# RS232.net
KiCad netlist of a schematic drawn in Altium Designer
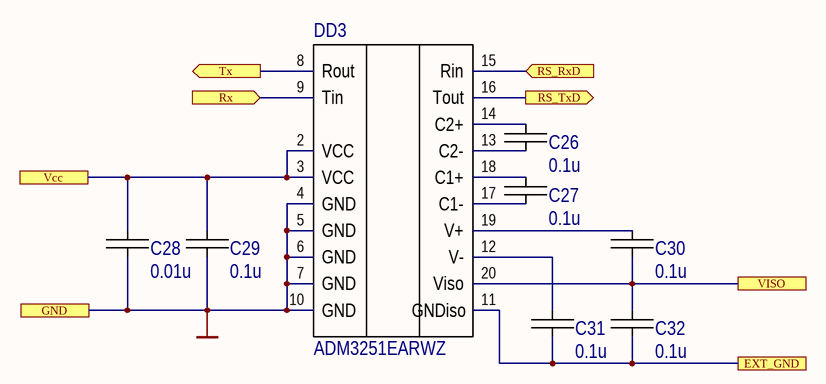
[diagram p0: RS232.SchDoc]

(export (version "E")
  (design (tool "Eeschema 10.0.6"))
  (components
    (comp (ref "C26")
      (value "0.1u")
      (footprint "C0603_IPC")
      (description "0.1uF ±10% 50V Ceramic Capacitor X7R 0603 (1608 Metric)")
      (fields (field (name "PARTNUMBER") "0.1u 50V") (field (name "MPN") "CL10B104KB8NNND"))
      (libsource (lib "DB_res_cap_ind") (part "C0603_GOST"))
    )
    (comp (ref "C27")
      (value "0.1u")
      (footprint "C0603_IPC")
      (description "0.1uF ±10% 50V Ceramic Capacitor X7R 0603 (1608 Metric)")
      (fields (field (name "PARTNUMBER") "0.1u 50V") (field (name "MPN") "CL10B104KB8NNND"))
      (libsource (lib "DB_res_cap_ind") (part "C0603_GOST"))
    )
    (comp (ref "C28")
      (value "0.01u")
      (footprint "C0603_IPC")
      (description "0.01uF ±10% 50V Ceramic Capacitor X7R 0603 (1608 Metric)")
      (fields (field (name "MPN") "CC0603KRX7R9BB103") (field (name "TOLERANCE") "0,1"))
      (libsource (lib "DB_res_cap_ind") (part "C0603_GOST"))
    )
    (comp (ref "C29")
      (value "0.1u")
      (footprint "C0603_IPC")
      (description "0.1uF ±10% 50V Ceramic Capacitor X7R 0603 (1608 Metric)")
      (fields (field (name "PARTNUMBER") "0.1u 50V") (field (name "MPN") "CL10B104KB8NNND"))
      (libsource (lib "DB_res_cap_ind") (part "C0603_GOST"))
    )
    (comp (ref "C30")
      (value "0.1u")
      (footprint "C0603_IPC")
      (description "0.1uF ±10% 50V Ceramic Capacitor X7R 0603 (1608 Metric)")
      (fields (field (name "PARTNUMBER") "0.1u 50V") (field (name "MPN") "CL10B104KB8NNND"))
      (libsource (lib "DB_res_cap_ind") (part "C0603_GOST"))
    )
    (comp (ref "C31")
      (value "0.1u")
      (footprint "C0603_IPC")
      (description "0.1uF ±10% 50V Ceramic Capacitor X7R 0603 (1608 Metric)")
      (fields (field (name "PARTNUMBER") "0.1u 50V") (field (name "MPN") "CL10B104KB8NNND"))
      (libsource (lib "DB_res_cap_ind") (part "C0603_GOST"))
    )
    (comp (ref "C32")
      (value "0.1u")
      (footprint "C0603_IPC")
      (description "0.1uF ±10% 50V Ceramic Capacitor X7R 0603 (1608 Metric)")
      (fields (field (name "PARTNUMBER") "0.1u 50V") (field (name "MPN") "CL10B104KB8NNND"))
      (libsource (lib "DB_res_cap_ind") (part "C0603_GOST"))
    )
    (comp (ref "DD3")
      (value "ADM3251EARWZ")
      (footprint "SOIC20W")
      (description "Isolated, Single-Channel RS-232 Line Driver/Receiver")
      (libsource (lib "DB_IC") (part "ADM3251E"))
    )
  )
  (nets
    (net (code "1") (name "/EXT_GND") (class "Default")
      (node (ref "C31") (pin "1") (pinfunction "1_1") (pintype "passive"))
      (node (ref "C32") (pin "1") (pinfunction "1_1") (pintype "passive"))
      (node (ref "DD3") (pin "11") (pinfunction "GNDiso_11") (pintype "passive"))
    )
    (net (code "2") (name "/RS_RxD") (class "Default")
      (node (ref "DD3") (pin "15") (pinfunction "Rin_15") (pintype "passive"))
    )
    (net (code "3") (name "/RS_TxD") (class "Default")
      (node (ref "DD3") (pin "16") (pinfunction "Tout_16") (pintype "passive"))
    )
    (net (code "4") (name "/Rx") (class "Default")
      (node (ref "DD3") (pin "9") (pinfunction "Tin_9") (pintype "passive"))
    )
    (net (code "5") (name "/Tx") (class "Default")
      (node (ref "DD3") (pin "8") (pinfunction "Rout_8") (pintype "passive"))
    )
    (net (code "6") (name "/VISO") (class "Default")
      (node (ref "C30") (pin "1") (pinfunction "1_1") (pintype "passive"))
      (node (ref "C32") (pin "2") (pinfunction "2_2") (pintype "passive"))
      (node (ref "DD3") (pin "20") (pinfunction "Viso_20") (pintype "passive"))
    )
    (net (code "7") (name "/Vcc") (class "Default")
      (node (ref "C28") (pin "1") (pinfunction "1_1") (pintype "passive"))
      (node (ref "C29") (pin "2") (pinfunction "2_2") (pintype "passive"))
      (node (ref "DD3") (pin "2") (pinfunction "VCC_2") (pintype "passive"))
      (node (ref "DD3") (pin "3") (pinfunction "VCC_3") (pintype "passive"))
    )
    (net (code "8") (name "GND") (class "Default")
      (node (ref "C28") (pin "2") (pinfunction "2_2") (pintype "passive"))
      (node (ref "C29") (pin "1") (pinfunction "1_1") (pintype "passive"))
      (node (ref "DD3") (pin "10") (pinfunction "GND_10") (pintype "passive"))
      (node (ref "DD3") (pin "4") (pinfunction "GND_4") (pintype "passive"))
      (node (ref "DD3") (pin "5") (pinfunction "GND_5") (pintype "passive"))
      (node (ref "DD3") (pin "6") (pinfunction "GND_6") (pintype "passive"))
      (node (ref "DD3") (pin "7") (pinfunction "GND_7") (pintype "passive"))
    )
    (net (code "9") (name "Net-(DD3-C1+)") (class "Default")
      (node (ref "C27") (pin "2") (pinfunction "2_2") (pintype "passive"))
      (node (ref "DD3") (pin "18") (pinfunction "C1+_18") (pintype "passive"))
    )
    (net (code "10") (name "Net-(DD3-C1-)") (class "Default")
      (node (ref "C27") (pin "1") (pinfunction "1_1") (pintype "passive"))
      (node (ref "DD3") (pin "17") (pinfunction "C1-_17") (pintype "passive"))
    )
    (net (code "11") (name "Net-(DD3-C2+)") (class "Default")
      (node (ref "C26") (pin "2") (pinfunction "2_2") (pintype "passive"))
      (node (ref "DD3") (pin "14") (pinfunction "C2+_14") (pintype "passive"))
    )
    (net (code "12") (name "Net-(DD3-C2-)") (class "Default")
      (node (ref "C26") (pin "1") (pinfunction "1_1") (pintype "passive"))
      (node (ref "DD3") (pin "13") (pinfunction "C2-_13") (pintype "passive"))
    )
    (net (code "13") (name "Net-(DD3-V+)") (class "Default")
      (node (ref "C30") (pin "2") (pinfunction "2_2") (pintype "passive"))
      (node (ref "DD3") (pin "19") (pinfunction "V+_19") (pintype "passive"))
    )
    (net (code "14") (name "Net-(DD3-V-)") (class "Default")
      (node (ref "C31") (pin "2") (pinfunction "2_2") (pintype "passive"))
      (node (ref "DD3") (pin "12") (pinfunction "V-_12") (pintype "passive"))
    )
    (net (code "15") (name "unconnected-(DD3-NC-Pad1)") (class "Default")
      (node (ref "DD3") (pin "1") (pinfunction "NC_1") (pintype "passive"))
    )
    (net (code "16") (name "unconnected-(DD3-NC-Pad2)") (class "Default")
      (node (ref "DD3") (pin "2") (pinfunction "NC_2") (pintype "tri_state"))
    )
  )
)
